# shield_008.net
KiCad netlist of a schematic drawn in EAGLE
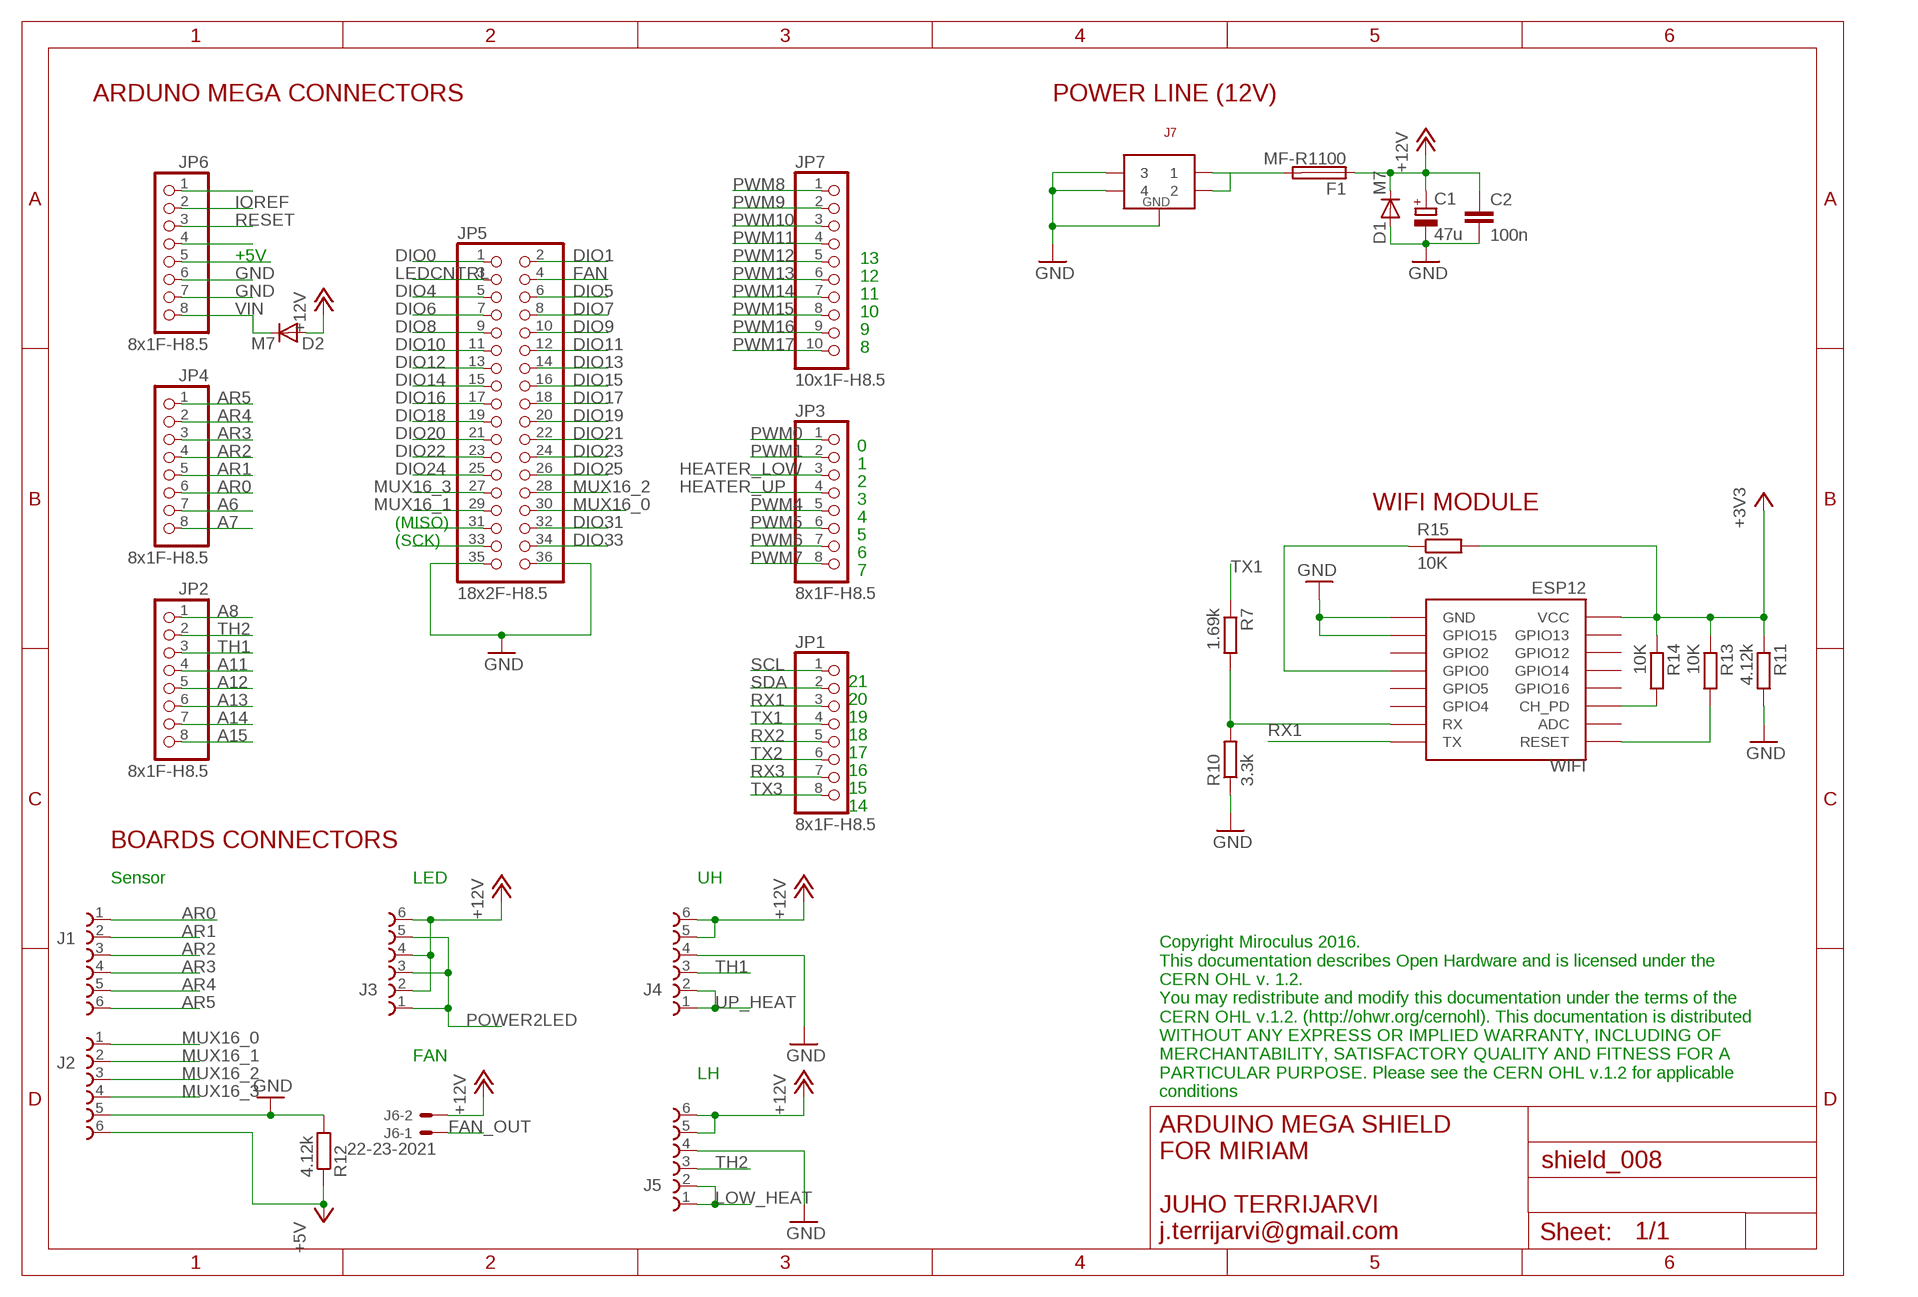
[diagram p0: schematic, sheet 1, part 1 of 2]
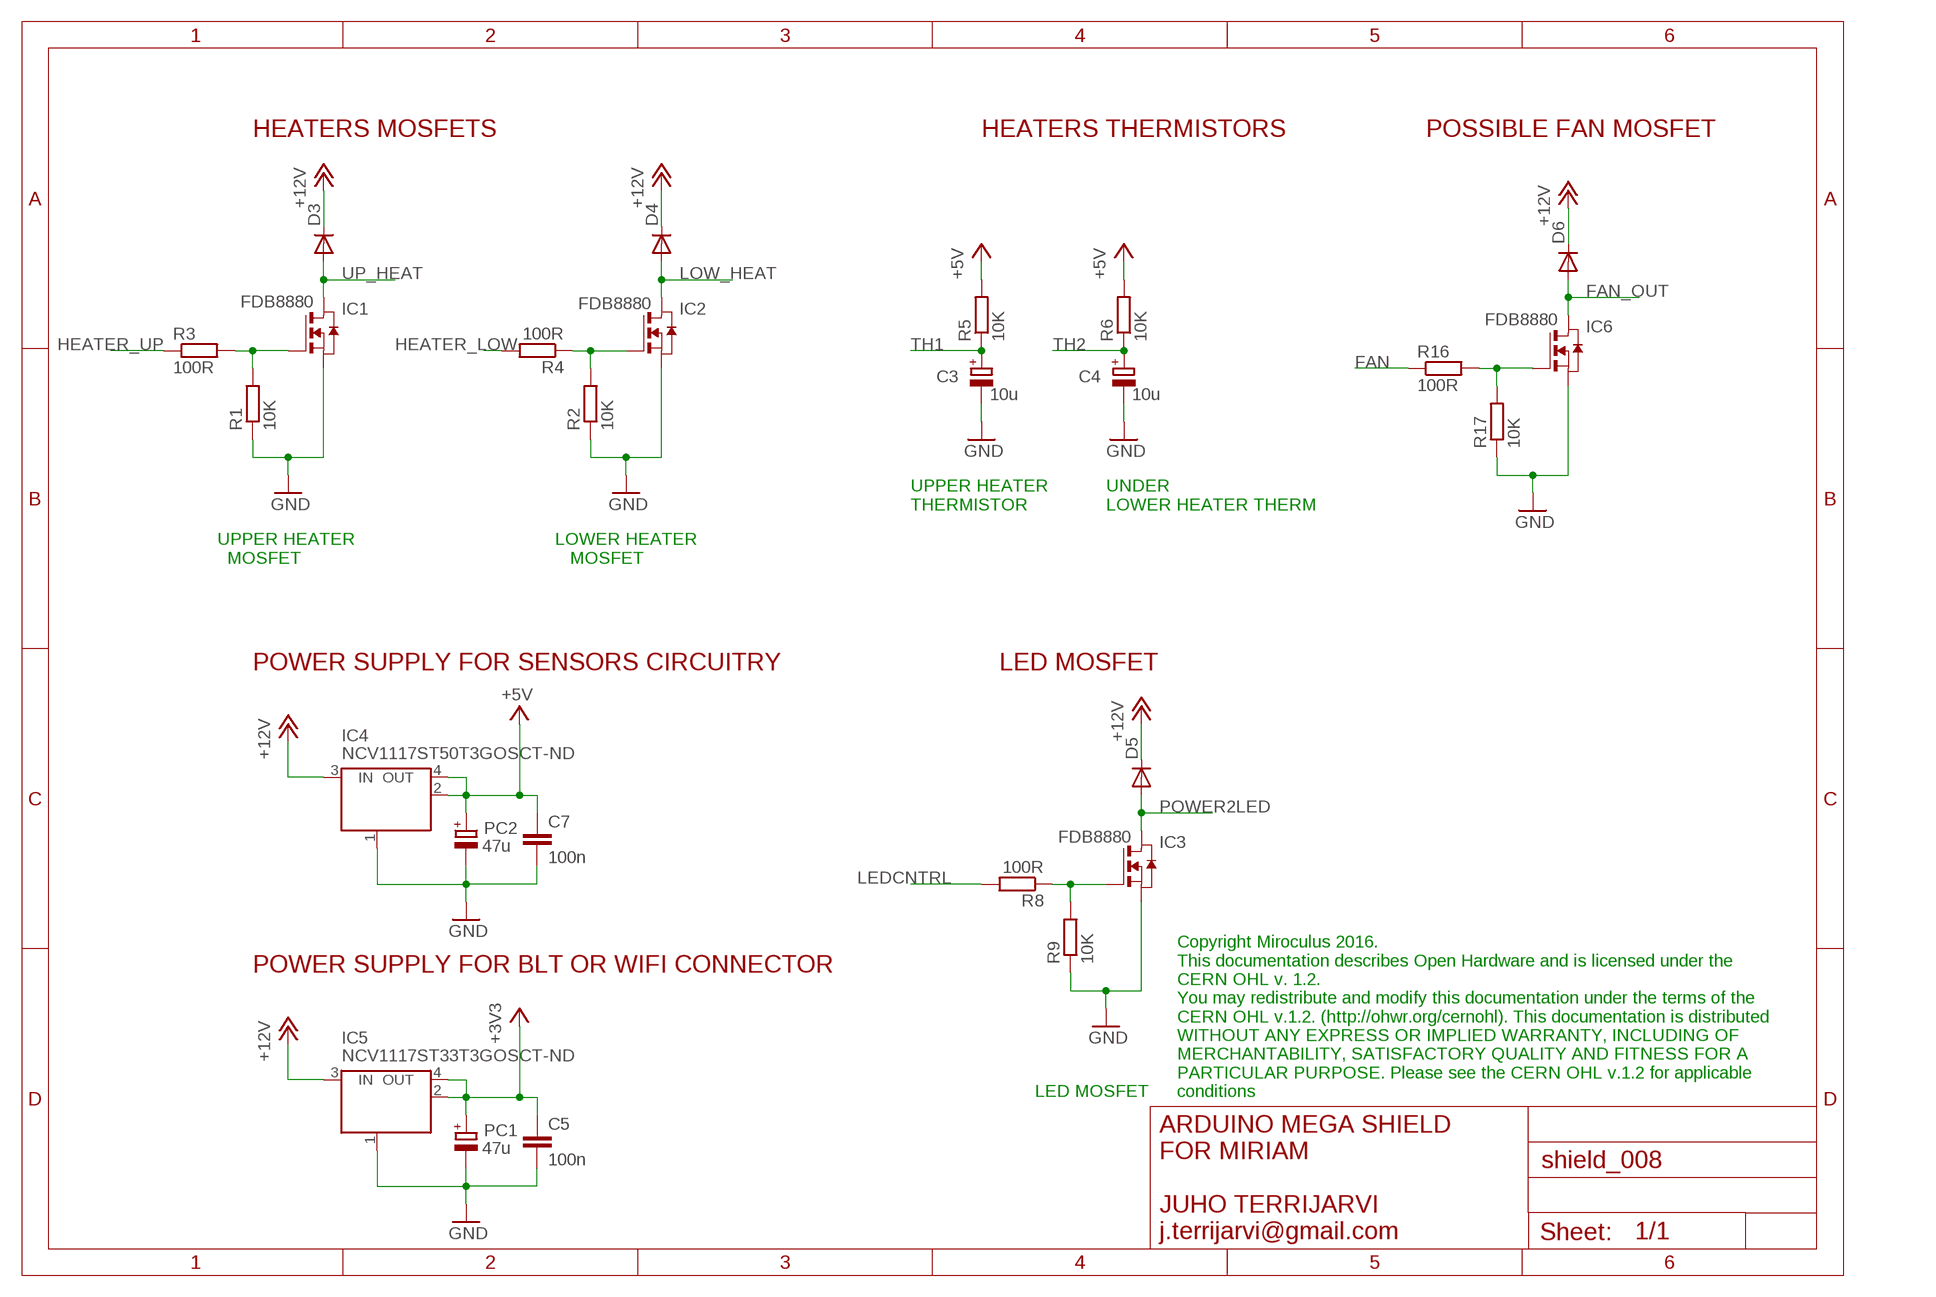
[diagram p1: schematic, sheet 1, part 2 of 2]

(export (version "E")
  (design (tool "Eeschema 10.0.6"))
  (components
    (comp (ref "C1")
      (value "47u")
      (footprint "eagle-import:PANASONIC_D")
      (libsource (lib "eagle-import") (part "CPOL-EUD"))
    )
    (comp (ref "C2")
      (value "100n")
      (footprint "eagle-import:C0603")
      (libsource (lib "eagle-import") (part "C-EUC0603"))
    )
    (comp (ref "C3")
      (value "10u")
      (footprint "eagle-import:A_3216-18R")
      (libsource (lib "eagle-import") (part "CPOL-EUA/3216-18R"))
    )
    (comp (ref "C4")
      (value "10u")
      (footprint "eagle-import:A_3216-18R")
      (libsource (lib "eagle-import") (part "CPOL-EUA/3216-18R"))
    )
    (comp (ref "C5")
      (value "100n")
      (footprint "eagle-import:C0603")
      (libsource (lib "eagle-import") (part "C-EUC0603"))
    )
    (comp (ref "C7")
      (value "100n")
      (footprint "eagle-import:C0603")
      (libsource (lib "eagle-import") (part "C-EUC0603"))
    )
    (comp (ref "D1")
      (value "M7")
      (footprint "eagle-import:SMB")
      (libsource (lib "eagle-import") (part "DIODE-SMB"))
    )
    (comp (ref "D2")
      (value "M7")
      (footprint "eagle-import:SMB")
      (libsource (lib "eagle-import") (part "DIODE-SMB"))
    )
    (comp (ref "D3")
      (value "RGL34A")
      (footprint "eagle-import:DO-213AA_DIODE")
      (libsource (lib "eagle-import") (part "DO-213_DIODE"))
    )
    (comp (ref "D4")
      (value "RGL34A")
      (footprint "eagle-import:DO-213AA_DIODE")
      (libsource (lib "eagle-import") (part "DO-213_DIODE"))
    )
    (comp (ref "D5")
      (value "RGL34A")
      (footprint "eagle-import:DO-213AA_DIODE")
      (libsource (lib "eagle-import") (part "DO-213_DIODE"))
    )
    (comp (ref "D6")
      (value "RGL34A")
      (footprint "eagle-import:DO-213AA_DIODE")
      (libsource (lib "eagle-import") (part "DO-213_DIODE"))
    )
    (comp (ref "F1")
      (value "MF-R1100")
      (footprint "eagle-import:LITTLEFUSE")
      (libsource (lib "eagle-import") (part "LITTLEFUSE"))
    )
    (comp (ref "IC1")
      (value "FDB8880")
      (footprint "eagle-import:FDB8880")
      (libsource (lib "eagle-import") (part "FDB8880"))
    )
    (comp (ref "IC2")
      (value "FDB8880")
      (footprint "eagle-import:FDB8880")
      (libsource (lib "eagle-import") (part "FDB8880"))
    )
    (comp (ref "IC3")
      (value "FDB8880")
      (footprint "eagle-import:FDB8880")
      (libsource (lib "eagle-import") (part "FDB8880"))
    )
    (comp (ref "IC4")
      (value "NCV1117ST50T3GOSCT-ND")
      (footprint "eagle-import:SOT223")
      (libsource (lib "eagle-import") (part "MC33269ST-3.3T3"))
    )
    (comp (ref "IC5")
      (value "NCV1117ST33T3GOSCT-ND")
      (footprint "eagle-import:SOT223")
      (libsource (lib "eagle-import") (part "MC33269ST-3.3T3"))
    )
    (comp (ref "IC6")
      (value "FDB8880")
      (footprint "eagle-import:FDB8880")
      (libsource (lib "eagle-import") (part "FDB8880"))
    )
    (comp (ref "J1")
      (value "68710614522")
      (footprint "eagle-import:68710614522")
      (libsource (lib "eagle-import") (part "68710614522"))
    )
    (comp (ref "J2")
      (value "68710614522")
      (footprint "eagle-import:68710614522")
      (libsource (lib "eagle-import") (part "68710614522"))
    )
    (comp (ref "J3")
      (value "68710614522")
      (footprint "eagle-import:68710614522")
      (libsource (lib "eagle-import") (part "68710614522"))
    )
    (comp (ref "J4")
      (value "68710614522")
      (footprint "eagle-import:68710614522")
      (libsource (lib "eagle-import") (part "68710614522"))
    )
    (comp (ref "J5")
      (value "68710614522")
      (footprint "eagle-import:68710614522")
      (libsource (lib "eagle-import") (part "68710614522"))
    )
    (comp (ref "J6")
      (value "22-23-2021")
      (footprint "eagle-import:22-23-2021")
      (fields (field (name "MF") "MOLEX"))
      (libsource (lib "eagle-import") (part "22-23-2021"))
    )
    (comp (ref "J7")
      (value "KPJX-4S-S")
      (footprint "eagle-import:KPJX-4S-S")
      (fields (field (name "MF") "Kycon"))
      (libsource (lib "eagle-import") (part "KPJX-4S-S"))
    )
    (comp (ref "JP1")
      (value "8x1F-H8.5")
      (footprint "eagle-import:1X08")
      (libsource (lib "eagle-import") (part "PINHD-1X8"))
    )
    (comp (ref "JP2")
      (value "8x1F-H8.5")
      (footprint "eagle-import:1X08")
      (libsource (lib "eagle-import") (part "PINHD-1X8"))
    )
    (comp (ref "JP3")
      (value "8x1F-H8.5")
      (footprint "eagle-import:1X08")
      (libsource (lib "eagle-import") (part "PINHD-1X8"))
    )
    (comp (ref "JP4")
      (value "8x1F-H8.5")
      (footprint "eagle-import:1X08")
      (libsource (lib "eagle-import") (part "PINHD-1X8"))
    )
    (comp (ref "JP5")
      (value "18x2F-H8.5")
      (footprint "eagle-import:2X18")
      (libsource (lib "eagle-import") (part "PINHD-2X18"))
    )
    (comp (ref "JP6")
      (value "8x1F-H8.5")
      (footprint "eagle-import:1X08")
      (libsource (lib "eagle-import") (part "PINHD-1X8"))
    )
    (comp (ref "JP7")
      (value "10x1F-H8.5")
      (footprint "eagle-import:1X10")
      (libsource (lib "eagle-import") (part "PINHD-1X10_ARD"))
    )
    (comp (ref "PC1")
      (value "47u")
      (footprint "eagle-import:PANASONIC_D")
      (libsource (lib "eagle-import") (part "CPOL-EUD"))
    )
    (comp (ref "PC2")
      (value "47u")
      (footprint "eagle-import:PANASONIC_D")
      (libsource (lib "eagle-import") (part "CPOL-EUD"))
    )
    (comp (ref "R1")
      (value "10K")
      (footprint "eagle-import:R0603")
      (libsource (lib "eagle-import") (part "R-EU_R0603"))
    )
    (comp (ref "R2")
      (value "10K")
      (footprint "eagle-import:R0603")
      (libsource (lib "eagle-import") (part "R-EU_R0603"))
    )
    (comp (ref "R3")
      (value "100R")
      (footprint "eagle-import:R0603")
      (libsource (lib "eagle-import") (part "R-EU_R0603"))
    )
    (comp (ref "R4")
      (value "100R")
      (footprint "eagle-import:R0603")
      (libsource (lib "eagle-import") (part "R-EU_R0603"))
    )
    (comp (ref "R5")
      (value "10K")
      (footprint "eagle-import:R0603")
      (libsource (lib "eagle-import") (part "R-EU_R0603"))
    )
    (comp (ref "R6")
      (value "10K")
      (footprint "eagle-import:R0603")
      (libsource (lib "eagle-import") (part "R-EU_R0603"))
    )
    (comp (ref "R7")
      (value "1.69k")
      (footprint "eagle-import:R0603")
      (libsource (lib "eagle-import") (part "R-EU_R0603"))
    )
    (comp (ref "R8")
      (value "100R")
      (footprint "eagle-import:R0603")
      (libsource (lib "eagle-import") (part "R-EU_R0603"))
    )
    (comp (ref "R9")
      (value "10K")
      (footprint "eagle-import:R0603")
      (libsource (lib "eagle-import") (part "R-EU_R0603"))
    )
    (comp (ref "R10")
      (value "3.3k")
      (footprint "eagle-import:R0603")
      (libsource (lib "eagle-import") (part "R-EU_R0603"))
    )
    (comp (ref "R11")
      (value "4.12k")
      (footprint "eagle-import:R0603")
      (libsource (lib "eagle-import") (part "R-EU_R0603"))
    )
    (comp (ref "R12")
      (value "4.12k")
      (footprint "eagle-import:R0603")
      (libsource (lib "eagle-import") (part "R-EU_R0603"))
    )
    (comp (ref "R13")
      (value "10K")
      (footprint "eagle-import:R0603")
      (libsource (lib "eagle-import") (part "R-EU_R0603"))
    )
    (comp (ref "R14")
      (value "10K")
      (footprint "eagle-import:R0603")
      (libsource (lib "eagle-import") (part "R-EU_R0603"))
    )
    (comp (ref "R15")
      (value "10K")
      (footprint "eagle-import:R0603")
      (libsource (lib "eagle-import") (part "R-EU_R0603"))
    )
    (comp (ref "R16")
      (value "100R")
      (footprint "eagle-import:R0603")
      (libsource (lib "eagle-import") (part "R-EU_R0603"))
    )
    (comp (ref "R17")
      (value "10K")
      (footprint "eagle-import:R0603")
      (libsource (lib "eagle-import") (part "R-EU_R0603"))
    )
    (comp (ref "WIFI")
      (value "ESP12")
      (footprint "eagle-import:ESP12")
      (libsource (lib "eagle-import") (part "ESP12"))
    )
  )
  (nets
    (net (code "1") (name "+3V3") (class "Default")
      (node (ref "C5") (pin "1") (pinfunction "1_1") (pintype "passive"))
      (node (ref "IC5") (pin "2") (pinfunction "OUT_2") (pintype "passive"))
      (node (ref "IC5") (pin "4") (pinfunction "OUT_4") (pintype "passive"))
      (node (ref "PC1") (pin "+") (pinfunction "+_+") (pintype "passive"))
      (node (ref "R11") (pin "1") (pinfunction "1_1") (pintype "passive"))
      (node (ref "R13") (pin "1") (pinfunction "1_1") (pintype "passive"))
      (node (ref "R14") (pin "1") (pinfunction "1_1") (pintype "passive"))
      (node (ref "R15") (pin "2") (pinfunction "2_2") (pintype "passive"))
      (node (ref "WIFI") (pin "VCC") (pinfunction "VCC_VCC") (pintype "bidirectional"))
    )
    (net (code "2") (name "+5V") (class "Default")
      (node (ref "C7") (pin "1") (pinfunction "1_1") (pintype "passive"))
      (node (ref "IC4") (pin "2") (pinfunction "OUT_2") (pintype "passive"))
      (node (ref "IC4") (pin "4") (pinfunction "OUT_4") (pintype "passive"))
      (node (ref "J2") (pin "6") (pinfunction "6_6") (pintype "passive"))
      (node (ref "PC2") (pin "+") (pinfunction "+_+") (pintype "passive"))
      (node (ref "R12") (pin "1") (pinfunction "1_1") (pintype "passive"))
      (node (ref "R5") (pin "2") (pinfunction "2_2") (pintype "passive"))
      (node (ref "R6") (pin "2") (pinfunction "2_2") (pintype "passive"))
    )
    (net (code "3") (name "+12V") (class "Default")
      (node (ref "C1") (pin "+") (pinfunction "+_+") (pintype "passive"))
      (node (ref "C2") (pin "1") (pinfunction "1_1") (pintype "passive"))
      (node (ref "D1") (pin "C") (pinfunction "C_C") (pintype "passive"))
      (node (ref "D2") (pin "A") (pinfunction "A_A") (pintype "passive"))
      (node (ref "D3") (pin "P$2") (pinfunction "C_P$2") (pintype "passive"))
      (node (ref "D4") (pin "P$2") (pinfunction "C_P$2") (pintype "passive"))
      (node (ref "D5") (pin "P$2") (pinfunction "C_P$2") (pintype "passive"))
      (node (ref "D6") (pin "P$2") (pinfunction "C_P$2") (pintype "passive"))
      (node (ref "F1") (pin "1") (pinfunction "1_1") (pintype "passive"))
      (node (ref "IC4") (pin "3") (pinfunction "IN_3") (pintype "input"))
      (node (ref "IC5") (pin "3") (pinfunction "IN_3") (pintype "input"))
      (node (ref "J3") (pin "2") (pinfunction "2_2") (pintype "passive"))
      (node (ref "J3") (pin "4") (pinfunction "4_4") (pintype "passive"))
      (node (ref "J3") (pin "6") (pinfunction "6_6") (pintype "passive"))
      (node (ref "J4") (pin "5") (pinfunction "5_5") (pintype "passive"))
      (node (ref "J4") (pin "6") (pinfunction "6_6") (pintype "passive"))
      (node (ref "J5") (pin "5") (pinfunction "5_5") (pintype "passive"))
      (node (ref "J5") (pin "6") (pinfunction "6_6") (pintype "passive"))
      (node (ref "J6") (pin "2") (pinfunction "S_2") (pintype "passive"))
    )
    (net (code "4") (name "/A6") (class "Default")
      (node (ref "JP4") (pin "7") (pinfunction "7_7") (pintype "passive"))
    )
    (net (code "5") (name "/A7") (class "Default")
      (node (ref "JP4") (pin "8") (pinfunction "8_8") (pintype "passive"))
    )
    (net (code "6") (name "/A8") (class "Default")
      (node (ref "JP2") (pin "1") (pinfunction "1_1") (pintype "passive"))
    )
    (net (code "7") (name "/A11") (class "Default")
      (node (ref "JP2") (pin "4") (pinfunction "4_4") (pintype "passive"))
    )
    (net (code "8") (name "/A12") (class "Default")
      (node (ref "JP2") (pin "5") (pinfunction "5_5") (pintype "passive"))
    )
    (net (code "9") (name "/A13") (class "Default")
      (node (ref "JP2") (pin "6") (pinfunction "6_6") (pintype "passive"))
    )
    (net (code "10") (name "/A14") (class "Default")
      (node (ref "JP2") (pin "7") (pinfunction "7_7") (pintype "passive"))
    )
    (net (code "11") (name "/A15") (class "Default")
      (node (ref "JP2") (pin "8") (pinfunction "8_8") (pintype "passive"))
    )
    (net (code "12") (name "/AR0") (class "Default")
      (node (ref "J1") (pin "1") (pinfunction "1_1") (pintype "passive"))
      (node (ref "JP4") (pin "6") (pinfunction "6_6") (pintype "passive"))
    )
    (net (code "13") (name "/AR1") (class "Default")
      (node (ref "J1") (pin "2") (pinfunction "2_2") (pintype "passive"))
      (node (ref "JP4") (pin "5") (pinfunction "5_5") (pintype "passive"))
    )
    (net (code "14") (name "/AR2") (class "Default")
      (node (ref "J1") (pin "3") (pinfunction "3_3") (pintype "passive"))
      (node (ref "JP4") (pin "4") (pinfunction "4_4") (pintype "passive"))
    )
    (net (code "15") (name "/AR3") (class "Default")
      (node (ref "J1") (pin "4") (pinfunction "4_4") (pintype "passive"))
      (node (ref "JP4") (pin "3") (pinfunction "3_3") (pintype "passive"))
    )
    (net (code "16") (name "/AR4") (class "Default")
      (node (ref "J1") (pin "5") (pinfunction "5_5") (pintype "passive"))
      (node (ref "JP4") (pin "2") (pinfunction "2_2") (pintype "passive"))
    )
    (net (code "17") (name "/AR5") (class "Default")
      (node (ref "J1") (pin "6") (pinfunction "6_6") (pintype "passive"))
      (node (ref "JP4") (pin "1") (pinfunction "1_1") (pintype "passive"))
    )
    (net (code "18") (name "/DIO0") (class "Default")
      (node (ref "JP5") (pin "1") (pinfunction "1_1") (pintype "passive"))
    )
    (net (code "19") (name "/DIO1") (class "Default")
      (node (ref "JP5") (pin "2") (pinfunction "2_2") (pintype "passive"))
    )
    (net (code "20") (name "/DIO4") (class "Default")
      (node (ref "JP5") (pin "5") (pinfunction "5_5") (pintype "passive"))
    )
    (net (code "21") (name "/DIO5") (class "Default")
      (node (ref "JP5") (pin "6") (pinfunction "6_6") (pintype "passive"))
    )
    (net (code "22") (name "/DIO6") (class "Default")
      (node (ref "JP5") (pin "7") (pinfunction "7_7") (pintype "passive"))
    )
    (net (code "23") (name "/DIO7") (class "Default")
      (node (ref "JP5") (pin "8") (pinfunction "8_8") (pintype "passive"))
    )
    (net (code "24") (name "/DIO8") (class "Default")
      (node (ref "JP5") (pin "9") (pinfunction "9_9") (pintype "passive"))
    )
    (net (code "25") (name "/DIO9") (class "Default")
      (node (ref "JP5") (pin "10") (pinfunction "10_10") (pintype "passive"))
    )
    (net (code "26") (name "/DIO10") (class "Default")
      (node (ref "JP5") (pin "11") (pinfunction "11_11") (pintype "passive"))
    )
    (net (code "27") (name "/DIO11") (class "Default")
      (node (ref "JP5") (pin "12") (pinfunction "12_12") (pintype "passive"))
    )
    (net (code "28") (name "/DIO12") (class "Default")
      (node (ref "JP5") (pin "13") (pinfunction "13_13") (pintype "passive"))
    )
    (net (code "29") (name "/DIO13") (class "Default")
      (node (ref "JP5") (pin "14") (pinfunction "14_14") (pintype "passive"))
    )
    (net (code "30") (name "/DIO14") (class "Default")
      (node (ref "JP5") (pin "15") (pinfunction "15_15") (pintype "passive"))
    )
    (net (code "31") (name "/DIO15") (class "Default")
      (node (ref "JP5") (pin "16") (pinfunction "16_16") (pintype "passive"))
    )
    (net (code "32") (name "/DIO16") (class "Default")
      (node (ref "JP5") (pin "17") (pinfunction "17_17") (pintype "passive"))
    )
    (net (code "33") (name "/DIO17") (class "Default")
      (node (ref "JP5") (pin "18") (pinfunction "18_18") (pintype "passive"))
    )
    (net (code "34") (name "/DIO18") (class "Default")
      (node (ref "JP5") (pin "19") (pinfunction "19_19") (pintype "passive"))
    )
    (net (code "35") (name "/DIO19") (class "Default")
      (node (ref "JP5") (pin "20") (pinfunction "20_20") (pintype "passive"))
    )
    (net (code "36") (name "/DIO20") (class "Default")
      (node (ref "JP5") (pin "21") (pinfunction "21_21") (pintype "passive"))
    )
    (net (code "37") (name "/DIO21") (class "Default")
      (node (ref "JP5") (pin "22") (pinfunction "22_22") (pintype "passive"))
    )
    (net (code "38") (name "/DIO22") (class "Default")
      (node (ref "JP5") (pin "23") (pinfunction "23_23") (pintype "passive"))
    )
    (net (code "39") (name "/DIO23") (class "Default")
      (node (ref "JP5") (pin "24") (pinfunction "24_24") (pintype "passive"))
    )
    (net (code "40") (name "/DIO24") (class "Default")
      (node (ref "JP5") (pin "25") (pinfunction "25_25") (pintype "passive"))
    )
    (net (code "41") (name "/DIO25") (class "Default")
      (node (ref "JP5") (pin "26") (pinfunction "26_26") (pintype "passive"))
    )
    (net (code "42") (name "/DIO31") (class "Default")
      (node (ref "JP5") (pin "32") (pinfunction "32_32") (pintype "passive"))
    )
    (net (code "43") (name "/DIO33") (class "Default")
      (node (ref "JP5") (pin "34") (pinfunction "34_34") (pintype "passive"))
    )
    (net (code "44") (name "/FAN") (class "Default")
      (node (ref "JP5") (pin "4") (pinfunction "4_4") (pintype "passive"))
      (node (ref "R16") (pin "1") (pinfunction "1_1") (pintype "passive"))
    )
    (net (code "45") (name "/FAN_OUT") (class "Default")
      (node (ref "D6") (pin "P$1") (pinfunction "A_P$1") (pintype "passive"))
      (node (ref "IC6") (pin "2") (pinfunction "D_2") (pintype "passive"))
      (node (ref "J6") (pin "1") (pinfunction "S_1") (pintype "passive"))
    )
    (net (code "46") (name "/HEATER_LOW") (class "Default")
      (node (ref "JP3") (pin "3") (pinfunction "3_3") (pintype "passive"))
      (node (ref "R4") (pin "2") (pinfunction "2_2") (pintype "passive"))
    )
    (net (code "47") (name "/HEATER_UP") (class "Default")
      (node (ref "JP3") (pin "4") (pinfunction "4_4") (pintype "passive"))
      (node (ref "R3") (pin "1") (pinfunction "1_1") (pintype "passive"))
    )
    (net (code "48") (name "/IOREF") (class "Default")
      (node (ref "JP6") (pin "2") (pinfunction "2_2") (pintype "passive"))
    )
    (net (code "49") (name "/LEDCNTRL") (class "Default")
      (node (ref "JP5") (pin "3") (pinfunction "3_3") (pintype "passive"))
      (node (ref "R8") (pin "2") (pinfunction "2_2") (pintype "passive"))
    )
    (net (code "50") (name "/LOW_HEAT") (class "Default")
      (node (ref "D4") (pin "P$1") (pinfunction "A_P$1") (pintype "passive"))
      (node (ref "IC2") (pin "2") (pinfunction "D_2") (pintype "passive"))
      (node (ref "J5") (pin "1") (pinfunction "1_1") (pintype "passive"))
      (node (ref "J5") (pin "2") (pinfunction "2_2") (pintype "passive"))
    )
    (net (code "51") (name "/MUX16_0") (class "Default")
      (node (ref "J2") (pin "1") (pinfunction "1_1") (pintype "passive"))
      (node (ref "JP5") (pin "30") (pinfunction "30_30") (pintype "passive"))
    )
    (net (code "52") (name "/MUX16_1") (class "Default")
      (node (ref "J2") (pin "2") (pinfunction "2_2") (pintype "passive"))
      (node (ref "JP5") (pin "29") (pinfunction "29_29") (pintype "passive"))
    )
    (net (code "53") (name "/MUX16_2") (class "Default")
      (node (ref "J2") (pin "3") (pinfunction "3_3") (pintype "passive"))
      (node (ref "JP5") (pin "28") (pinfunction "28_28") (pintype "passive"))
    )
    (net (code "54") (name "/MUX16_3") (class "Default")
      (node (ref "J2") (pin "4") (pinfunction "4_4") (pintype "passive"))
      (node (ref "JP5") (pin "27") (pinfunction "27_27") (pintype "passive"))
    )
    (net (code "55") (name "/POWER2LED") (class "Default")
      (node (ref "D5") (pin "P$1") (pinfunction "A_P$1") (pintype "passive"))
      (node (ref "IC3") (pin "2") (pinfunction "D_2") (pintype "passive"))
      (node (ref "J3") (pin "1") (pinfunction "1_1") (pintype "passive"))
      (node (ref "J3") (pin "3") (pinfunction "3_3") (pintype "passive"))
      (node (ref "J3") (pin "5") (pinfunction "5_5") (pintype "passive"))
    )
    (net (code "56") (name "/PWM0") (class "Default")
      (node (ref "JP3") (pin "1") (pinfunction "1_1") (pintype "passive"))
    )
    (net (code "57") (name "/PWM1") (class "Default")
      (node (ref "JP3") (pin "2") (pinfunction "2_2") (pintype "passive"))
    )
    (net (code "58") (name "/PWM4") (class "Default")
      (node (ref "JP3") (pin "5") (pinfunction "5_5") (pintype "passive"))
    )
    (net (code "59") (name "/PWM5") (class "Default")
      (node (ref "JP3") (pin "6") (pinfunction "6_6") (pintype "passive"))
    )
    (net (code "60") (name "/PWM6") (class "Default")
      (node (ref "JP3") (pin "7") (pinfunction "7_7") (pintype "passive"))
    )
    (net (code "61") (name "/PWM7") (class "Default")
      (node (ref "JP3") (pin "8") (pinfunction "8_8") (pintype "passive"))
    )
    (net (code "62") (name "/PWM8") (class "Default")
      (node (ref "JP7") (pin "1") (pinfunction "1_1") (pintype "passive"))
    )
    (net (code "63") (name "/PWM9") (class "Default")
      (node (ref "JP7") (pin "2") (pinfunction "2_2") (pintype "passive"))
    )
    (net (code "64") (name "/PWM10") (class "Default")
      (node (ref "JP7") (pin "3") (pinfunction "3_3") (pintype "passive"))
    )
    (net (code "65") (name "/PWM11") (class "Default")
      (node (ref "JP7") (pin "4") (pinfunction "4_4") (pintype "passive"))
    )
    (net (code "66") (name "/PWM12") (class "Default")
      (node (ref "JP7") (pin "5") (pinfunction "5_5") (pintype "passive"))
    )
    (net (code "67") (name "/PWM13") (class "Default")
      (node (ref "JP7") (pin "6") (pinfunction "6_6") (pintype "passive"))
    )
    (net (code "68") (name "/PWM14") (class "Default")
      (node (ref "JP7") (pin "7") (pinfunction "7_7") (pintype "passive"))
    )
    (net (code "69") (name "/PWM15") (class "Default")
      (node (ref "JP7") (pin "8") (pinfunction "8_8") (pintype "passive"))
    )
    (net (code "70") (name "/PWM16") (class "Default")
      (node (ref "JP7") (pin "9") (pinfunction "9_9") (pintype "passive"))
    )
    (net (code "71") (name "/PWM17") (class "Default")
      (node (ref "JP7") (pin "10") (pinfunction "10_10") (pintype "passive"))
    )
    (net (code "72") (name "/RESET") (class "Default")
      (node (ref "JP6") (pin "3") (pinfunction "3_3") (pintype "passive"))
    )
    (net (code "73") (name "/RX1") (class "Default")
      (node (ref "JP1") (pin "3") (pinfunction "3_3") (pintype "passive"))
      (node (ref "WIFI") (pin "TX") (pinfunction "TX_TX") (pintype "bidirectional"))
    )
    (net (code "74") (name "/RX2") (class "Default")
      (node (ref "JP1") (pin "5") (pinfunction "5_5") (pintype "passive"))
    )
    (net (code "75") (name "/RX3") (class "Default")
      (node (ref "JP1") (pin "7") (pinfunction "7_7") (pintype "passive"))
    )
    (net (code "76") (name "/SCL") (class "Default")
      (node (ref "JP1") (pin "1") (pinfunction "1_1") (pintype "passive"))
    )
    (net (code "77") (name "/SDA") (class "Default")
      (node (ref "JP1") (pin "2") (pinfunction "2_2") (pintype "passive"))
    )
    (net (code "78") (name "/TH1") (class "Default")
      (node (ref "C3") (pin "+") (pinfunction "+_+") (pintype "passive"))
      (node (ref "J4") (pin "3") (pinfunction "3_3") (pintype "passive"))
      (node (ref "JP2") (pin "3") (pinfunction "3_3") (pintype "passive"))
      (node (ref "R5") (pin "1") (pinfunction "1_1") (pintype "passive"))
    )
    (net (code "79") (name "/TH2") (class "Default")
      (node (ref "C4") (pin "+") (pinfunction "+_+") (pintype "passive"))
      (node (ref "J5") (pin "3") (pinfunction "3_3") (pintype "passive"))
      (node (ref "JP2") (pin "2") (pinfunction "2_2") (pintype "passive"))
      (node (ref "R6") (pin "1") (pinfunction "1_1") (pintype "passive"))
    )
    (net (code "80") (name "/TX1") (class "Default")
      (node (ref "JP1") (pin "4") (pinfunction "4_4") (pintype "passive"))
      (node (ref "R7") (pin "1") (pinfunction "1_1") (pintype "passive"))
    )
    (net (code "81") (name "/TX2") (class "Default")
      (node (ref "JP1") (pin "6") (pinfunction "6_6") (pintype "passive"))
    )
    (net (code "82") (name "/TX3") (class "Default")
      (node (ref "JP1") (pin "8") (pinfunction "8_8") (pintype "passive"))
    )
    (net (code "83") (name "/UP_HEAT") (class "Default")
      (node (ref "D3") (pin "P$1") (pinfunction "A_P$1") (pintype "passive"))
      (node (ref "IC1") (pin "2") (pinfunction "D_2") (pintype "passive"))
      (node (ref "J4") (pin "1") (pinfunction "1_1") (pintype "passive"))
      (node (ref "J4") (pin "2") (pinfunction "2_2") (pintype "passive"))
    )
    (net (code "84") (name "/VIN") (class "Default")
      (node (ref "D2") (pin "C") (pinfunction "C_C") (pintype "passive"))
      (node (ref "JP6") (pin "8") (pinfunction "8_8") (pintype "passive"))
    )
    (net (code "85") (name "GND") (class "Default")
      (node (ref "C1") (pin "-") (pinfunction "-_-") (pintype "passive"))
      (node (ref "C2") (pin "2") (pinfunction "2_2") (pintype "passive"))
      (node (ref "C3") (pin "-") (pinfunction "-_-") (pintype "passive"))
      (node (ref "C4") (pin "-") (pinfunction "-_-") (pintype "passive"))
      (node (ref "C5") (pin "2") (pinfunction "2_2") (pintype "passive"))
      (node (ref "C7") (pin "2") (pinfunction "2_2") (pintype "passive"))
      (node (ref "D1") (pin "A") (pinfunction "A_A") (pintype "passive"))
      (node (ref "IC1") (pin "3") (pinfunction "S_3") (pintype "passive"))
      (node (ref "IC2") (pin "3") (pinfunction "S_3") (pintype "passive"))
      (node (ref "IC3") (pin "3") (pinfunction "S_3") (pintype "passive"))
      (node (ref "IC4") (pin "1") (pinfunction "GND/ADJ_1") (pintype "input"))
      (node (ref "IC5") (pin "1") (pinfunction "GND/ADJ_1") (pintype "input"))
      (node (ref "IC6") (pin "3") (pinfunction "S_3") (pintype "passive"))
      (node (ref "J2") (pin "5") (pinfunction "5_5") (pintype "passive"))
      (node (ref "J4") (pin "4") (pinfunction "4_4") (pintype "passive"))
      (node (ref "J5") (pin "4") (pinfunction "4_4") (pintype "passive"))
      (node (ref "J7") (pin "P$3") (pinfunction "3_P$3") (pintype "bidirectional"))
      (node (ref "J7") (pin "P$4") (pinfunction "4_P$4") (pintype "bidirectional"))
      (node (ref "J7") (pin "P$5") (pinfunction "G_P$5") (pintype "bidirectional"))
      (node (ref "J7") (pin "P$6") (pinfunction "G_P$6") (pintype "bidirectional"))
      (node (ref "J7") (pin "P$7") (pinfunction "G_P$7") (pintype "bidirectional"))
      (node (ref "JP5") (pin "35") (pinfunction "35_35") (pintype "passive"))
      (node (ref "JP5") (pin "36") (pinfunction "36_36") (pintype "passive"))
      (node (ref "JP6") (pin "6") (pinfunction "6_6") (pintype "passive"))
      (node (ref "JP6") (pin "7") (pinfunction "7_7") (pintype "passive"))
      (node (ref "PC1") (pin "-") (pinfunction "-_-") (pintype "passive"))
      (node (ref "PC2") (pin "-") (pinfunction "-_-") (pintype "passive"))
      (node (ref "R1") (pin "1") (pinfunction "1_1") (pintype "passive"))
      (node (ref "R10") (pin "1") (pinfunction "1_1") (pintype "passive"))
      (node (ref "R11") (pin "2") (pinfunction "2_2") (pintype "passive"))
      (node (ref "R12") (pin "2") (pinfunction "2_2") (pintype "passive"))
      (node (ref "R17") (pin "1") (pinfunction "1_1") (pintype "passive"))
      (node (ref "R2") (pin "1") (pinfunction "1_1") (pintype "passive"))
      (node (ref "R9") (pin "1") (pinfunction "1_1") (pintype "passive"))
      (node (ref "WIFI") (pin "GND") (pinfunction "GND_GND") (pintype "bidirectional"))
      (node (ref "WIFI") (pin "GPIO15") (pinfunction "GPIO15_GPIO15") (pintype "bidirectional"))
    )
    (net (code "86") (name "Net-(IC1-G)") (class "Default")
      (node (ref "IC1") (pin "1") (pinfunction "G_1") (pintype "passive"))
      (node (ref "R1") (pin "2") (pinfunction "2_2") (pintype "passive"))
      (node (ref "R3") (pin "2") (pinfunction "2_2") (pintype "passive"))
    )
    (net (code "87") (name "Net-(IC2-G)") (class "Default")
      (node (ref "IC2") (pin "1") (pinfunction "G_1") (pintype "passive"))
      (node (ref "R2") (pin "2") (pinfunction "2_2") (pintype "passive"))
      (node (ref "R4") (pin "1") (pinfunction "1_1") (pintype "passive"))
    )
    (net (code "88") (name "Net-(IC3-G)") (class "Default")
      (node (ref "IC3") (pin "1") (pinfunction "G_1") (pintype "passive"))
      (node (ref "R8") (pin "1") (pinfunction "1_1") (pintype "passive"))
      (node (ref "R9") (pin "2") (pinfunction "2_2") (pintype "passive"))
    )
    (net (code "89") (name "Net-(IC6-G)") (class "Default")
      (node (ref "IC6") (pin "1") (pinfunction "G_1") (pintype "passive"))
      (node (ref "R16") (pin "2") (pinfunction "2_2") (pintype "passive"))
      (node (ref "R17") (pin "2") (pinfunction "2_2") (pintype "passive"))
    )
    (net (code "90") (name "Net-(J7-1)") (class "Default")
      (node (ref "F1") (pin "2") (pinfunction "2_2") (pintype "passive"))
      (node (ref "J7") (pin "P$1") (pinfunction "1_P$1") (pintype "bidirectional"))
      (node (ref "J7") (pin "P$2") (pinfunction "2_P$2") (pintype "bidirectional"))
    )
    (net (code "91") (name "Net-(R10-Pad2)") (class "Default")
      (node (ref "R10") (pin "2") (pinfunction "2_2") (pintype "passive"))
      (node (ref "R7") (pin "2") (pinfunction "2_2") (pintype "passive"))
      (node (ref "WIFI") (pin "RX") (pinfunction "RX_RX") (pintype "bidirectional"))
    )
    (net (code "92") (name "Net-(R13-Pad2)") (class "Default")
      (node (ref "R13") (pin "2") (pinfunction "2_2") (pintype "passive"))
      (node (ref "WIFI") (pin "RESET") (pinfunction "RESET_RESET") (pintype "bidirectional"))
    )
    (net (code "93") (name "Net-(R14-Pad2)") (class "Default")
      (node (ref "R14") (pin "2") (pinfunction "2_2") (pintype "passive"))
      (node (ref "WIFI") (pin "CH_PD") (pinfunction "CH_PD_CH_PD") (pintype "bidirectional"))
    )
    (net (code "94") (name "Net-(R15-Pad1)") (class "Default")
      (node (ref "R15") (pin "1") (pinfunction "1_1") (pintype "passive"))
      (node (ref "WIFI") (pin "GPIO0") (pinfunction "GPIO0_GPIO0") (pintype "bidirectional"))
    )
    (net (code "95") (name "unconnected-(JP5-Pad31)") (class "Default")
      (node (ref "JP5") (pin "31") (pinfunction "31_31") (pintype "passive"))
    )
    (net (code "96") (name "unconnected-(JP5-Pad33)") (class "Default")
      (node (ref "JP5") (pin "33") (pinfunction "33_33") (pintype "passive"))
    )
    (net (code "97") (name "unconnected-(JP6-Pad1)") (class "Default")
      (node (ref "JP6") (pin "1") (pinfunction "1_1") (pintype "passive"))
    )
    (net (code "98") (name "unconnected-(JP6-Pad4)") (class "Default")
      (node (ref "JP6") (pin "4") (pinfunction "4_4") (pintype "passive"))
    )
    (net (code "99") (name "unconnected-(JP6-Pad5)") (class "Default")
      (node (ref "JP6") (pin "5") (pinfunction "5_5") (pintype "passive"))
    )
    (net (code "100") (name "unconnected-(WIFI-PadADC)") (class "Default")
      (node (ref "WIFI") (pin "ADC") (pinfunction "ADC_ADC") (pintype "bidirectional"))
    )
    (net (code "101") (name "unconnected-(WIFI-PadGPIO2)") (class "Default")
      (node (ref "WIFI") (pin "GPIO2") (pinfunction "GPIO2_GPIO2") (pintype "bidirectional"))
    )
    (net (code "102") (name "unconnected-(WIFI-PadGPIO4)") (class "Default")
      (node (ref "WIFI") (pin "GPIO4") (pinfunction "GPIO4_GPIO4") (pintype "bidirectional"))
    )
    (net (code "103") (name "unconnected-(WIFI-PadGPIO5)") (class "Default")
      (node (ref "WIFI") (pin "GPIO5") (pinfunction "GPIO5_GPIO5") (pintype "bidirectional"))
    )
    (net (code "104") (name "unconnected-(WIFI-PadGPIO12)") (class "Default")
      (node (ref "WIFI") (pin "GPIO12") (pinfunction "GPIO12_GPIO12") (pintype "bidirectional"))
    )
    (net (code "105") (name "unconnected-(WIFI-PadGPIO13)") (class "Default")
      (node (ref "WIFI") (pin "GPIO13") (pinfunction "GPIO13_GPIO13") (pintype "bidirectional"))
    )
    (net (code "106") (name "unconnected-(WIFI-PadGPIO14)") (class "Default")
      (node (ref "WIFI") (pin "GPIO14") (pinfunction "GPIO14_GPIO14") (pintype "bidirectional"))
    )
    (net (code "107") (name "unconnected-(WIFI-PadGPIO16)") (class "Default")
      (node (ref "WIFI") (pin "GPIO16") (pinfunction "GPIO16_GPIO16") (pintype "bidirectional"))
    )
  )
)
